# shades_v30.net
KiCad netlist of a schematic drawn in EAGLE
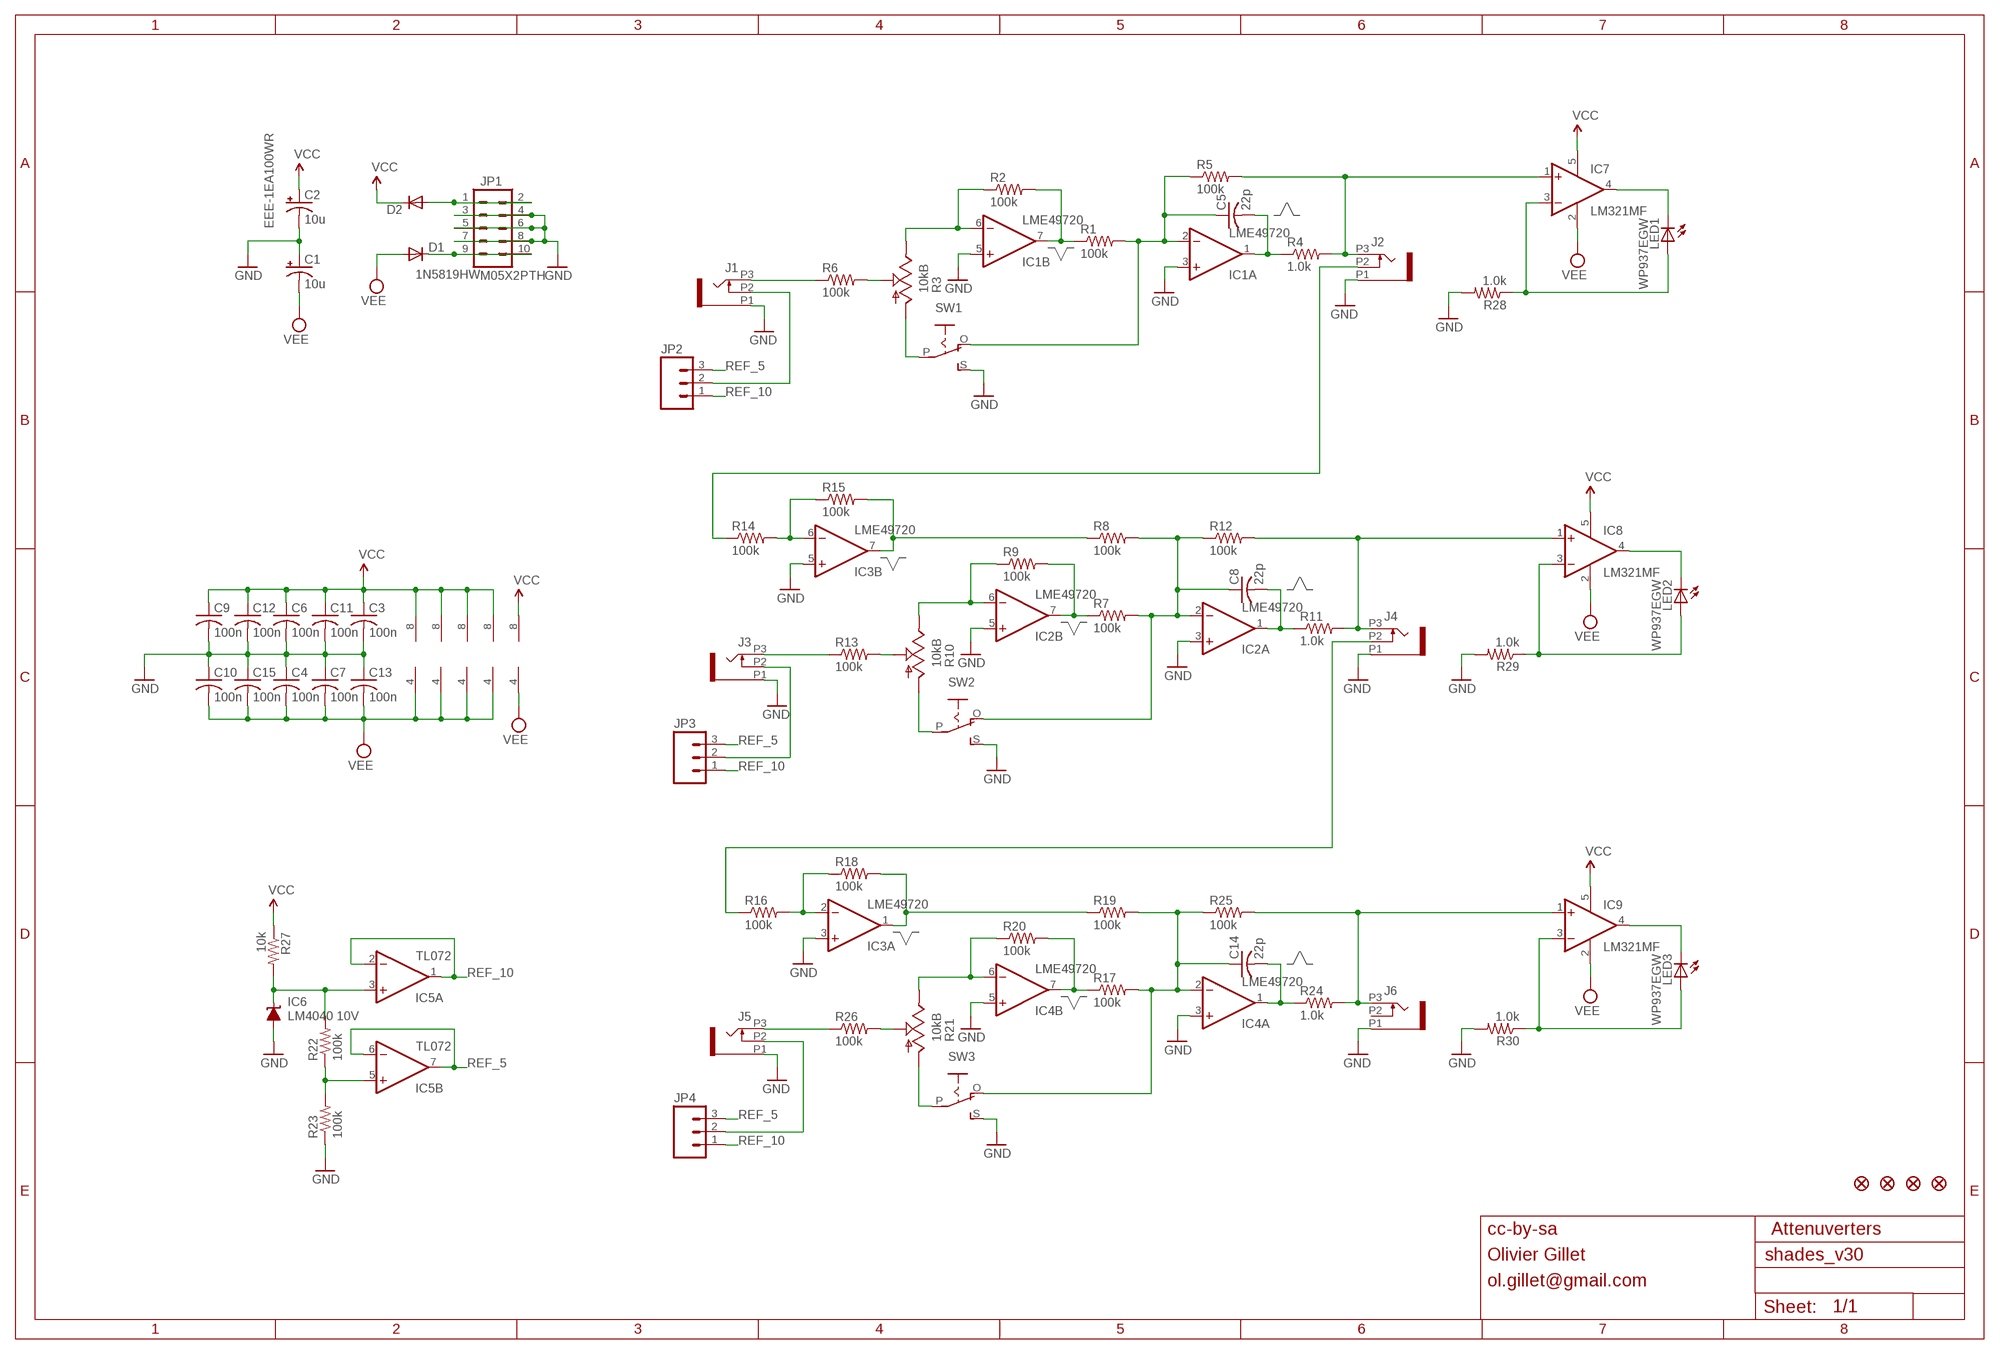
[diagram p0: schematic, sheet 1]

(export (version "E")
  (design (tool "Eeschema 10.0.6"))
  (components
    (comp (ref "C1")
      (value "10u")
      (footprint "eagle-import:PANASONIC_B")
      (libsource (lib "eagle-import") (part "CPOL-USB"))
    )
    (comp (ref "C2")
      (value "10u")
      (footprint "eagle-import:PANASONIC_B")
      (libsource (lib "eagle-import") (part "CPOL-USB"))
    )
    (comp (ref "C3")
      (value "100n")
      (footprint "eagle-import:C0603")
      (libsource (lib "eagle-import") (part "C-USC0603"))
    )
    (comp (ref "C4")
      (value "100n")
      (footprint "eagle-import:C0603")
      (libsource (lib "eagle-import") (part "C-USC0603"))
    )
    (comp (ref "C5")
      (value "22p")
      (footprint "eagle-import:C0603")
      (libsource (lib "eagle-import") (part "C-USC0603"))
    )
    (comp (ref "C6")
      (value "100n")
      (footprint "eagle-import:C0603")
      (libsource (lib "eagle-import") (part "C-USC0603"))
    )
    (comp (ref "C7")
      (value "100n")
      (footprint "eagle-import:C0603")
      (libsource (lib "eagle-import") (part "C-USC0603"))
    )
    (comp (ref "C8")
      (value "22p")
      (footprint "eagle-import:C0603")
      (libsource (lib "eagle-import") (part "C-USC0603"))
    )
    (comp (ref "C9")
      (value "100n")
      (footprint "eagle-import:C0603")
      (libsource (lib "eagle-import") (part "C-USC0603"))
    )
    (comp (ref "C10")
      (value "100n")
      (footprint "eagle-import:C0603")
      (libsource (lib "eagle-import") (part "C-USC0603"))
    )
    (comp (ref "C11")
      (value "100n")
      (footprint "eagle-import:C0603")
      (libsource (lib "eagle-import") (part "C-USC0603"))
    )
    (comp (ref "C12")
      (value "100n")
      (footprint "eagle-import:C0603")
      (libsource (lib "eagle-import") (part "C-USC0603"))
    )
    (comp (ref "C13")
      (value "100n")
      (footprint "eagle-import:C0603")
      (libsource (lib "eagle-import") (part "C-USC0603"))
    )
    (comp (ref "C14")
      (value "22p")
      (footprint "eagle-import:C0603")
      (libsource (lib "eagle-import") (part "C-USC0603"))
    )
    (comp (ref "C15")
      (value "100n")
      (footprint "eagle-import:C0603")
      (libsource (lib "eagle-import") (part "C-USC0603"))
    )
    (comp (ref "D1")
      (value "1N5819HW")
      (footprint "eagle-import:SOD123")
      (libsource (lib "eagle-import") (part "DIODE-SOD123"))
    )
    (comp (ref "D2")
      (value "1N5819HW")
      (footprint "eagle-import:SOD123")
      (libsource (lib "eagle-import") (part "DIODE-SOD123"))
    )
    (comp (ref "F1")
      (value "FIDUCIAL1X2")
      (footprint "eagle-import:FIDUCIAL-1X2")
      (libsource (lib "eagle-import") (part "FIDUCIAL1X2"))
    )
    (comp (ref "F2")
      (value "FIDUCIAL1X2")
      (footprint "eagle-import:FIDUCIAL-1X2")
      (libsource (lib "eagle-import") (part "FIDUCIAL1X2"))
    )
    (comp (ref "F3")
      (value "FIDUCIAL1X2")
      (footprint "eagle-import:FIDUCIAL-1X2")
      (libsource (lib "eagle-import") (part "FIDUCIAL1X2"))
    )
    (comp (ref "F4")
      (value "FIDUCIAL1X2")
      (footprint "eagle-import:FIDUCIAL-1X2")
      (libsource (lib "eagle-import") (part "FIDUCIAL1X2"))
    )
    (comp (ref "IC1")
      (value "LME49720")
      (footprint "eagle-import:SO08")
      (libsource (lib "eagle-import") (part "TL072D"))
    )
    (comp (ref "IC2")
      (value "LME49720")
      (footprint "eagle-import:SO08")
      (libsource (lib "eagle-import") (part "TL072D"))
    )
    (comp (ref "IC3")
      (value "LME49720")
      (footprint "eagle-import:SO08")
      (libsource (lib "eagle-import") (part "TL072D"))
    )
    (comp (ref "IC4")
      (value "LME49720")
      (footprint "eagle-import:SO08")
      (libsource (lib "eagle-import") (part "TL072D"))
    )
    (comp (ref "IC5")
      (value "TL072")
      (footprint "eagle-import:SO08")
      (libsource (lib "eagle-import") (part "TL072D"))
    )
    (comp (ref "IC6")
      (value "LM4040 10V")
      (footprint "eagle-import:DBZ_R-PDSO-G3")
      (libsource (lib "eagle-import") (part "LM4041DBZC12"))
    )
    (comp (ref "IC7")
      (value "LM321MF")
      (footprint "eagle-import:SOT23-5")
      (libsource (lib "eagle-import") (part "LM321?MF"))
    )
    (comp (ref "IC8")
      (value "LM321MF")
      (footprint "eagle-import:SOT23-5")
      (libsource (lib "eagle-import") (part "LM321?MF"))
    )
    (comp (ref "IC9")
      (value "LM321MF")
      (footprint "eagle-import:SOT23-5")
      (libsource (lib "eagle-import") (part "LM321?MF"))
    )
    (comp (ref "J1")
      (value "PJ301_THONKICONN6")
      (footprint "eagle-import:WQP_PJ_301M6")
      (libsource (lib "eagle-import") (part "PJ301_THONKICONN6"))
    )
    (comp (ref "J2")
      (value "PJ301_THONKICONN6")
      (footprint "eagle-import:WQP_PJ_301M6")
      (libsource (lib "eagle-import") (part "PJ301_THONKICONN6"))
    )
    (comp (ref "J3")
      (value "PJ301_THONKICONN6")
      (footprint "eagle-import:WQP_PJ_301M6")
      (libsource (lib "eagle-import") (part "PJ301_THONKICONN6"))
    )
    (comp (ref "J4")
      (value "PJ301_THONKICONN6")
      (footprint "eagle-import:WQP_PJ_301M6")
      (libsource (lib "eagle-import") (part "PJ301_THONKICONN6"))
    )
    (comp (ref "J5")
      (value "PJ301_THONKICONN6")
      (footprint "eagle-import:WQP_PJ_301M6")
      (libsource (lib "eagle-import") (part "PJ301_THONKICONN6"))
    )
    (comp (ref "J6")
      (value "PJ301_THONKICONN6")
      (footprint "eagle-import:WQP_PJ_301M6")
      (libsource (lib "eagle-import") (part "PJ301_THONKICONN6"))
    )
    (comp (ref "JP1")
      (value "M05X2PTH")
      (footprint "eagle-import:AVR_ICSP")
      (libsource (lib "eagle-import") (part "M05X2PTH"))
    )
    (comp (ref "JP2")
      (value "M03PTH")
      (footprint "eagle-import:1X03")
      (libsource (lib "eagle-import") (part "M03PTH"))
    )
    (comp (ref "JP3")
      (value "M03PTH")
      (footprint "eagle-import:1X03")
      (libsource (lib "eagle-import") (part "M03PTH"))
    )
    (comp (ref "JP4")
      (value "M03PTH")
      (footprint "eagle-import:1X03")
      (libsource (lib "eagle-import") (part "M03PTH"))
    )
    (comp (ref "LED1")
      (value "WP937EGW")
      (footprint "eagle-import:LED3MM")
      (libsource (lib "eagle-import") (part "LED3MM"))
    )
    (comp (ref "LED2")
      (value "WP937EGW")
      (footprint "eagle-import:LED3MM")
      (libsource (lib "eagle-import") (part "LED3MM"))
    )
    (comp (ref "LED3")
      (value "WP937EGW")
      (footprint "eagle-import:LED3MM")
      (libsource (lib "eagle-import") (part "LED3MM"))
    )
    (comp (ref "R1")
      (value "100k")
      (footprint "eagle-import:R0603")
      (libsource (lib "eagle-import") (part "R-US_R0603"))
    )
    (comp (ref "R2")
      (value "100k")
      (footprint "eagle-import:R0603")
      (libsource (lib "eagle-import") (part "R-US_R0603"))
    )
    (comp (ref "R3")
      (value "10kB")
      (footprint "eagle-import:ALPS_POT_VERTICAL_PS")
      (libsource (lib "eagle-import") (part "POT_USVERTICAL_PS"))
    )
    (comp (ref "R4")
      (value "1.0k")
      (footprint "eagle-import:R0603")
      (libsource (lib "eagle-import") (part "R-US_R0603"))
    )
    (comp (ref "R5")
      (value "100k")
      (footprint "eagle-import:R0603")
      (libsource (lib "eagle-import") (part "R-US_R0603"))
    )
    (comp (ref "R6")
      (value "100k")
      (footprint "eagle-import:R0603")
      (libsource (lib "eagle-import") (part "R-US_R0603"))
    )
    (comp (ref "R7")
      (value "100k")
      (footprint "eagle-import:R0603")
      (libsource (lib "eagle-import") (part "R-US_R0603"))
    )
    (comp (ref "R8")
      (value "100k")
      (footprint "eagle-import:R0603")
      (libsource (lib "eagle-import") (part "R-US_R0603"))
    )
    (comp (ref "R9")
      (value "100k")
      (footprint "eagle-import:R0603")
      (libsource (lib "eagle-import") (part "R-US_R0603"))
    )
    (comp (ref "R10")
      (value "10kB")
      (footprint "eagle-import:ALPS_POT_VERTICAL_PS")
      (libsource (lib "eagle-import") (part "POT_USVERTICAL_PS"))
    )
    (comp (ref "R11")
      (value "1.0k")
      (footprint "eagle-import:R0603")
      (libsource (lib "eagle-import") (part "R-US_R0603"))
    )
    (comp (ref "R12")
      (value "100k")
      (footprint "eagle-import:R0603")
      (libsource (lib "eagle-import") (part "R-US_R0603"))
    )
    (comp (ref "R13")
      (value "100k")
      (footprint "eagle-import:R0603")
      (libsource (lib "eagle-import") (part "R-US_R0603"))
    )
    (comp (ref "R14")
      (value "100k")
      (footprint "eagle-import:R0603")
      (libsource (lib "eagle-import") (part "R-US_R0603"))
    )
    (comp (ref "R15")
      (value "100k")
      (footprint "eagle-import:R0603")
      (libsource (lib "eagle-import") (part "R-US_R0603"))
    )
    (comp (ref "R16")
      (value "100k")
      (footprint "eagle-import:R0603")
      (libsource (lib "eagle-import") (part "R-US_R0603"))
    )
    (comp (ref "R17")
      (value "100k")
      (footprint "eagle-import:R0603")
      (libsource (lib "eagle-import") (part "R-US_R0603"))
    )
    (comp (ref "R18")
      (value "100k")
      (footprint "eagle-import:R0603")
      (libsource (lib "eagle-import") (part "R-US_R0603"))
    )
    (comp (ref "R19")
      (value "100k")
      (footprint "eagle-import:R0603")
      (libsource (lib "eagle-import") (part "R-US_R0603"))
    )
    (comp (ref "R20")
      (value "100k")
      (footprint "eagle-import:R0603")
      (libsource (lib "eagle-import") (part "R-US_R0603"))
    )
    (comp (ref "R21")
      (value "10kB")
      (footprint "eagle-import:ALPS_POT_VERTICAL_PS")
      (libsource (lib "eagle-import") (part "POT_USVERTICAL_PS"))
    )
    (comp (ref "R22")
      (value "100k")
      (footprint "eagle-import:R0603")
      (libsource (lib "eagle-import") (part "R-US_R0603"))
    )
    (comp (ref "R23")
      (value "100k")
      (footprint "eagle-import:R0603")
      (libsource (lib "eagle-import") (part "R-US_R0603"))
    )
    (comp (ref "R24")
      (value "1.0k")
      (footprint "eagle-import:R0603")
      (libsource (lib "eagle-import") (part "R-US_R0603"))
    )
    (comp (ref "R25")
      (value "100k")
      (footprint "eagle-import:R0603")
      (libsource (lib "eagle-import") (part "R-US_R0603"))
    )
    (comp (ref "R26")
      (value "100k")
      (footprint "eagle-import:R0603")
      (libsource (lib "eagle-import") (part "R-US_R0603"))
    )
    (comp (ref "R27")
      (value "10k")
      (footprint "eagle-import:R0603")
      (libsource (lib "eagle-import") (part "resistor_R-US_R0603"))
    )
    (comp (ref "R28")
      (value "1.0k")
      (footprint "eagle-import:R0603")
      (libsource (lib "eagle-import") (part "R-US_R0603"))
    )
    (comp (ref "R29")
      (value "1.0k")
      (footprint "eagle-import:R0603")
      (libsource (lib "eagle-import") (part "R-US_R0603"))
    )
    (comp (ref "R30")
      (value "1.0k")
      (footprint "eagle-import:R0603")
      (libsource (lib "eagle-import") (part "R-US_R0603"))
    )
    (comp (ref "SW1")
      (value "S-ON-ONSMALL_SLIDE")
      (footprint "eagle-import:ES_100SP1T6B11M2QEH_SMALL")
      (libsource (lib "eagle-import") (part "S-ON-ONSMALL_SLIDE"))
    )
    (comp (ref "SW2")
      (value "S-ON-ONSMALL_SLIDE")
      (footprint "eagle-import:ES_100SP1T6B11M2QEH_SMALL")
      (libsource (lib "eagle-import") (part "S-ON-ONSMALL_SLIDE"))
    )
    (comp (ref "SW3")
      (value "S-ON-ONSMALL_SLIDE")
      (footprint "eagle-import:ES_100SP1T6B11M2QEH_SMALL")
      (libsource (lib "eagle-import") (part "S-ON-ONSMALL_SLIDE"))
    )
  )
  (nets
    (net (code "1") (name "/REF_5") (class "Default")
      (node (ref "IC5") (pin "6") (pinfunction "-IN_6") (pintype "input"))
      (node (ref "IC5") (pin "7") (pinfunction "OUT_7") (pintype "output"))
      (node (ref "JP2") (pin "3") (pinfunction "3_3") (pintype "passive"))
      (node (ref "JP3") (pin "3") (pinfunction "3_3") (pintype "passive"))
      (node (ref "JP4") (pin "3") (pinfunction "3_3") (pintype "passive"))
    )
    (net (code "2") (name "/REF_10") (class "Default")
      (node (ref "IC5") (pin "1") (pinfunction "OUT_1") (pintype "output"))
      (node (ref "IC5") (pin "2") (pinfunction "-IN_2") (pintype "input"))
      (node (ref "JP2") (pin "1") (pinfunction "1_1") (pintype "passive"))
      (node (ref "JP3") (pin "1") (pinfunction "1_1") (pintype "passive"))
      (node (ref "JP4") (pin "1") (pinfunction "1_1") (pintype "passive"))
    )
    (net (code "3") (name "GND") (class "Default")
      (node (ref "C1") (pin "+") (pinfunction "+_+") (pintype "passive"))
      (node (ref "C10") (pin "1") (pinfunction "1_1") (pintype "passive"))
      (node (ref "C11") (pin "2") (pinfunction "2_2") (pintype "passive"))
      (node (ref "C12") (pin "2") (pinfunction "2_2") (pintype "passive"))
      (node (ref "C13") (pin "1") (pinfunction "1_1") (pintype "passive"))
      (node (ref "C15") (pin "1") (pinfunction "1_1") (pintype "passive"))
      (node (ref "C2") (pin "-") (pinfunction "-_-") (pintype "passive"))
      (node (ref "C3") (pin "2") (pinfunction "2_2") (pintype "passive"))
      (node (ref "C4") (pin "1") (pinfunction "1_1") (pintype "passive"))
      (node (ref "C6") (pin "2") (pinfunction "2_2") (pintype "passive"))
      (node (ref "C7") (pin "1") (pinfunction "1_1") (pintype "passive"))
      (node (ref "C9") (pin "2") (pinfunction "2_2") (pintype "passive"))
      (node (ref "IC1") (pin "3") (pinfunction "+IN_3") (pintype "input"))
      (node (ref "IC1") (pin "5") (pinfunction "+IN_5") (pintype "input"))
      (node (ref "IC2") (pin "3") (pinfunction "+IN_3") (pintype "input"))
      (node (ref "IC2") (pin "5") (pinfunction "+IN_5") (pintype "input"))
      (node (ref "IC3") (pin "3") (pinfunction "+IN_3") (pintype "input"))
      (node (ref "IC3") (pin "5") (pinfunction "+IN_5") (pintype "input"))
      (node (ref "IC4") (pin "3") (pinfunction "+IN_3") (pintype "input"))
      (node (ref "IC4") (pin "5") (pinfunction "+IN_5") (pintype "input"))
      (node (ref "IC6") (pin "2") (pinfunction "A_2") (pintype "passive"))
      (node (ref "J1") (pin "P1") (pinfunction "1_P1") (pintype "passive"))
      (node (ref "J2") (pin "P1") (pinfunction "1_P1") (pintype "passive"))
      (node (ref "J3") (pin "P1") (pinfunction "1_P1") (pintype "passive"))
      (node (ref "J4") (pin "P1") (pinfunction "1_P1") (pintype "passive"))
      (node (ref "J5") (pin "P1") (pinfunction "1_P1") (pintype "passive"))
      (node (ref "J6") (pin "P1") (pinfunction "1_P1") (pintype "passive"))
      (node (ref "JP1") (pin "3") (pinfunction "3_3") (pintype "passive"))
      (node (ref "JP1") (pin "4") (pinfunction "4_4") (pintype "passive"))
      (node (ref "JP1") (pin "5") (pinfunction "5_5") (pintype "passive"))
      (node (ref "JP1") (pin "6") (pinfunction "6_6") (pintype "passive"))
      (node (ref "JP1") (pin "7") (pinfunction "7_7") (pintype "passive"))
      (node (ref "JP1") (pin "8") (pinfunction "8_8") (pintype "passive"))
      (node (ref "R23") (pin "1") (pinfunction "1_1") (pintype "passive"))
      (node (ref "R28") (pin "2") (pinfunction "2_2") (pintype "passive"))
      (node (ref "R29") (pin "2") (pinfunction "2_2") (pintype "passive"))
      (node (ref "R30") (pin "2") (pinfunction "2_2") (pintype "passive"))
      (node (ref "SW1") (pin "S") (pinfunction "S_S") (pintype "passive"))
      (node (ref "SW2") (pin "S") (pinfunction "S_S") (pintype "passive"))
      (node (ref "SW3") (pin "S") (pinfunction "S_S") (pintype "passive"))
    )
    (net (code "4") (name "Net-(D1-PadC)") (class "Default")
      (node (ref "D1") (pin "C") (pinfunction "C_C") (pintype "passive"))
      (node (ref "JP1") (pin "10") (pinfunction "10_10") (pintype "passive"))
      (node (ref "JP1") (pin "9") (pinfunction "9_9") (pintype "passive"))
    )
    (net (code "5") (name "Net-(D2-PadA)") (class "Default")
      (node (ref "D2") (pin "A") (pinfunction "A_A") (pintype "passive"))
      (node (ref "JP1") (pin "1") (pinfunction "1_1") (pintype "passive"))
      (node (ref "JP1") (pin "2") (pinfunction "2_2") (pintype "passive"))
    )
    (net (code "6") (name "Net-(IC1A--IN)") (class "Default")
      (node (ref "C5") (pin "1") (pinfunction "1_1") (pintype "passive"))
      (node (ref "IC1") (pin "2") (pinfunction "-IN_2") (pintype "input"))
      (node (ref "R1") (pin "2") (pinfunction "2_2") (pintype "passive"))
      (node (ref "R5") (pin "1") (pinfunction "1_1") (pintype "passive"))
      (node (ref "SW1") (pin "O") (pinfunction "O_O") (pintype "passive"))
    )
    (net (code "7") (name "Net-(IC1A-OUT)") (class "Default")
      (node (ref "C5") (pin "2") (pinfunction "2_2") (pintype "passive"))
      (node (ref "IC1") (pin "1") (pinfunction "OUT_1") (pintype "output"))
      (node (ref "R4") (pin "1") (pinfunction "1_1") (pintype "passive"))
    )
    (net (code "8") (name "Net-(IC1B--IN)") (class "Default")
      (node (ref "IC1") (pin "6") (pinfunction "-IN_6") (pintype "input"))
      (node (ref "R2") (pin "1") (pinfunction "1_1") (pintype "passive"))
      (node (ref "R3") (pin "P$1") (pinfunction "E_P$1") (pintype "passive"))
    )
    (net (code "9") (name "Net-(IC1B-OUT)") (class "Default")
      (node (ref "IC1") (pin "7") (pinfunction "OUT_7") (pintype "output"))
      (node (ref "R1") (pin "1") (pinfunction "1_1") (pintype "passive"))
      (node (ref "R2") (pin "2") (pinfunction "2_2") (pintype "passive"))
    )
    (net (code "10") (name "Net-(IC2A--IN)") (class "Default")
      (node (ref "C8") (pin "1") (pinfunction "1_1") (pintype "passive"))
      (node (ref "IC2") (pin "2") (pinfunction "-IN_2") (pintype "input"))
      (node (ref "R12") (pin "1") (pinfunction "1_1") (pintype "passive"))
      (node (ref "R7") (pin "2") (pinfunction "2_2") (pintype "passive"))
      (node (ref "R8") (pin "2") (pinfunction "2_2") (pintype "passive"))
      (node (ref "SW2") (pin "O") (pinfunction "O_O") (pintype "passive"))
    )
    (net (code "11") (name "Net-(IC2A-OUT)") (class "Default")
      (node (ref "C8") (pin "2") (pinfunction "2_2") (pintype "passive"))
      (node (ref "IC2") (pin "1") (pinfunction "OUT_1") (pintype "output"))
      (node (ref "R11") (pin "1") (pinfunction "1_1") (pintype "passive"))
    )
    (net (code "12") (name "Net-(IC2B--IN)") (class "Default")
      (node (ref "IC2") (pin "6") (pinfunction "-IN_6") (pintype "input"))
      (node (ref "R10") (pin "P$1") (pinfunction "E_P$1") (pintype "passive"))
      (node (ref "R9") (pin "1") (pinfunction "1_1") (pintype "passive"))
    )
    (net (code "13") (name "Net-(IC2B-OUT)") (class "Default")
      (node (ref "IC2") (pin "7") (pinfunction "OUT_7") (pintype "output"))
      (node (ref "R7") (pin "1") (pinfunction "1_1") (pintype "passive"))
      (node (ref "R9") (pin "2") (pinfunction "2_2") (pintype "passive"))
    )
    (net (code "14") (name "Net-(IC3A--IN)") (class "Default")
      (node (ref "IC3") (pin "2") (pinfunction "-IN_2") (pintype "input"))
      (node (ref "R16") (pin "2") (pinfunction "2_2") (pintype "passive"))
      (node (ref "R18") (pin "1") (pinfunction "1_1") (pintype "passive"))
    )
    (net (code "15") (name "Net-(IC3A-OUT)") (class "Default")
      (node (ref "IC3") (pin "1") (pinfunction "OUT_1") (pintype "output"))
      (node (ref "R18") (pin "2") (pinfunction "2_2") (pintype "passive"))
      (node (ref "R19") (pin "1") (pinfunction "1_1") (pintype "passive"))
    )
    (net (code "16") (name "Net-(IC3B--IN)") (class "Default")
      (node (ref "IC3") (pin "6") (pinfunction "-IN_6") (pintype "input"))
      (node (ref "R14") (pin "2") (pinfunction "2_2") (pintype "passive"))
      (node (ref "R15") (pin "1") (pinfunction "1_1") (pintype "passive"))
    )
    (net (code "17") (name "Net-(IC3B-OUT)") (class "Default")
      (node (ref "IC3") (pin "7") (pinfunction "OUT_7") (pintype "output"))
      (node (ref "R15") (pin "2") (pinfunction "2_2") (pintype "passive"))
      (node (ref "R8") (pin "1") (pinfunction "1_1") (pintype "passive"))
    )
    (net (code "18") (name "Net-(IC4A--IN)") (class "Default")
      (node (ref "C14") (pin "1") (pinfunction "1_1") (pintype "passive"))
      (node (ref "IC4") (pin "2") (pinfunction "-IN_2") (pintype "input"))
      (node (ref "R17") (pin "2") (pinfunction "2_2") (pintype "passive"))
      (node (ref "R19") (pin "2") (pinfunction "2_2") (pintype "passive"))
      (node (ref "R25") (pin "1") (pinfunction "1_1") (pintype "passive"))
      (node (ref "SW3") (pin "O") (pinfunction "O_O") (pintype "passive"))
    )
    (net (code "19") (name "Net-(IC4A-OUT)") (class "Default")
      (node (ref "C14") (pin "2") (pinfunction "2_2") (pintype "passive"))
      (node (ref "IC4") (pin "1") (pinfunction "OUT_1") (pintype "output"))
      (node (ref "R24") (pin "1") (pinfunction "1_1") (pintype "passive"))
    )
    (net (code "20") (name "Net-(IC4B--IN)") (class "Default")
      (node (ref "IC4") (pin "6") (pinfunction "-IN_6") (pintype "input"))
      (node (ref "R20") (pin "1") (pinfunction "1_1") (pintype "passive"))
      (node (ref "R21") (pin "P$1") (pinfunction "E_P$1") (pintype "passive"))
    )
    (net (code "21") (name "Net-(IC4B-OUT)") (class "Default")
      (node (ref "IC4") (pin "7") (pinfunction "OUT_7") (pintype "output"))
      (node (ref "R17") (pin "1") (pinfunction "1_1") (pintype "passive"))
      (node (ref "R20") (pin "2") (pinfunction "2_2") (pintype "passive"))
    )
    (net (code "22") (name "Net-(IC5A-+IN)") (class "Default")
      (node (ref "IC5") (pin "3") (pinfunction "+IN_3") (pintype "input"))
      (node (ref "IC6") (pin "1") (pinfunction "C_1") (pintype "passive"))
      (node (ref "R22") (pin "2") (pinfunction "2_2") (pintype "passive"))
      (node (ref "R27") (pin "2") (pinfunction "2_2") (pintype "passive"))
    )
    (net (code "23") (name "Net-(IC5B-+IN)") (class "Default")
      (node (ref "IC5") (pin "5") (pinfunction "+IN_5") (pintype "input"))
      (node (ref "R22") (pin "1") (pinfunction "1_1") (pintype "passive"))
      (node (ref "R23") (pin "2") (pinfunction "2_2") (pintype "passive"))
    )
    (net (code "24") (name "Net-(IC7-+IN)") (class "Default")
      (node (ref "IC7") (pin "1") (pinfunction "+IN_1") (pintype "input"))
      (node (ref "J2") (pin "P3") (pinfunction "3_P3") (pintype "passive"))
      (node (ref "R4") (pin "2") (pinfunction "2_2") (pintype "passive"))
      (node (ref "R5") (pin "2") (pinfunction "2_2") (pintype "passive"))
    )
    (net (code "25") (name "Net-(IC7--IN)") (class "Default")
      (node (ref "IC7") (pin "3") (pinfunction "-IN_3") (pintype "input"))
      (node (ref "LED1") (pin "A") (pinfunction "A_A") (pintype "passive"))
      (node (ref "R28") (pin "1") (pinfunction "1_1") (pintype "passive"))
    )
    (net (code "26") (name "Net-(IC7-OUT)") (class "Default")
      (node (ref "IC7") (pin "4") (pinfunction "OUT_4") (pintype "output"))
      (node (ref "LED1") (pin "K") (pinfunction "C_K") (pintype "passive"))
    )
    (net (code "27") (name "Net-(IC8-+IN)") (class "Default")
      (node (ref "IC8") (pin "1") (pinfunction "+IN_1") (pintype "input"))
      (node (ref "J4") (pin "P3") (pinfunction "3_P3") (pintype "passive"))
      (node (ref "R11") (pin "2") (pinfunction "2_2") (pintype "passive"))
      (node (ref "R12") (pin "2") (pinfunction "2_2") (pintype "passive"))
    )
    (net (code "28") (name "Net-(IC8--IN)") (class "Default")
      (node (ref "IC8") (pin "3") (pinfunction "-IN_3") (pintype "input"))
      (node (ref "LED2") (pin "A") (pinfunction "A_A") (pintype "passive"))
      (node (ref "R29") (pin "1") (pinfunction "1_1") (pintype "passive"))
    )
    (net (code "29") (name "Net-(IC8-OUT)") (class "Default")
      (node (ref "IC8") (pin "4") (pinfunction "OUT_4") (pintype "output"))
      (node (ref "LED2") (pin "K") (pinfunction "C_K") (pintype "passive"))
    )
    (net (code "30") (name "Net-(IC9-+IN)") (class "Default")
      (node (ref "IC9") (pin "1") (pinfunction "+IN_1") (pintype "input"))
      (node (ref "J6") (pin "P3") (pinfunction "3_P3") (pintype "passive"))
      (node (ref "R24") (pin "2") (pinfunction "2_2") (pintype "passive"))
      (node (ref "R25") (pin "2") (pinfunction "2_2") (pintype "passive"))
    )
    (net (code "31") (name "Net-(IC9--IN)") (class "Default")
      (node (ref "IC9") (pin "3") (pinfunction "-IN_3") (pintype "input"))
      (node (ref "LED3") (pin "A") (pinfunction "A_A") (pintype "passive"))
      (node (ref "R30") (pin "1") (pinfunction "1_1") (pintype "passive"))
    )
    (net (code "32") (name "Net-(IC9-OUT)") (class "Default")
      (node (ref "IC9") (pin "4") (pinfunction "OUT_4") (pintype "output"))
      (node (ref "LED3") (pin "K") (pinfunction "C_K") (pintype "passive"))
    )
    (net (code "33") (name "Net-(J1-2)") (class "Default")
      (node (ref "J1") (pin "P2") (pinfunction "2_P2") (pintype "passive"))
      (node (ref "JP2") (pin "2") (pinfunction "2_2") (pintype "passive"))
    )
    (net (code "34") (name "Net-(J1-3)") (class "Default")
      (node (ref "J1") (pin "P3") (pinfunction "3_P3") (pintype "passive"))
      (node (ref "R6") (pin "1") (pinfunction "1_1") (pintype "passive"))
    )
    (net (code "35") (name "Net-(J2-2)") (class "Default")
      (node (ref "J2") (pin "P2") (pinfunction "2_P2") (pintype "passive"))
      (node (ref "R14") (pin "1") (pinfunction "1_1") (pintype "passive"))
    )
    (net (code "36") (name "Net-(J3-2)") (class "Default")
      (node (ref "J3") (pin "P2") (pinfunction "2_P2") (pintype "passive"))
      (node (ref "JP3") (pin "2") (pinfunction "2_2") (pintype "passive"))
    )
    (net (code "37") (name "Net-(J3-3)") (class "Default")
      (node (ref "J3") (pin "P3") (pinfunction "3_P3") (pintype "passive"))
      (node (ref "R13") (pin "1") (pinfunction "1_1") (pintype "passive"))
    )
    (net (code "38") (name "Net-(J4-2)") (class "Default")
      (node (ref "J4") (pin "P2") (pinfunction "2_P2") (pintype "passive"))
      (node (ref "R16") (pin "1") (pinfunction "1_1") (pintype "passive"))
    )
    (net (code "39") (name "Net-(J5-2)") (class "Default")
      (node (ref "J5") (pin "P2") (pinfunction "2_P2") (pintype "passive"))
      (node (ref "JP4") (pin "2") (pinfunction "2_2") (pintype "passive"))
    )
    (net (code "40") (name "Net-(J5-3)") (class "Default")
      (node (ref "J5") (pin "P3") (pinfunction "3_P3") (pintype "passive"))
      (node (ref "R26") (pin "1") (pinfunction "1_1") (pintype "passive"))
    )
    (net (code "41") (name "Net-(R3-A)") (class "Default")
      (node (ref "R3") (pin "P$3") (pinfunction "A_P$3") (pintype "passive"))
      (node (ref "SW1") (pin "P") (pinfunction "P_P") (pintype "passive"))
    )
    (net (code "42") (name "Net-(R3-S)") (class "Default")
      (node (ref "R3") (pin "P$2") (pinfunction "S_P$2") (pintype "passive"))
      (node (ref "R6") (pin "2") (pinfunction "2_2") (pintype "passive"))
    )
    (net (code "43") (name "Net-(R10-A)") (class "Default")
      (node (ref "R10") (pin "P$3") (pinfunction "A_P$3") (pintype "passive"))
      (node (ref "SW2") (pin "P") (pinfunction "P_P") (pintype "passive"))
    )
    (net (code "44") (name "Net-(R10-S)") (class "Default")
      (node (ref "R10") (pin "P$2") (pinfunction "S_P$2") (pintype "passive"))
      (node (ref "R13") (pin "2") (pinfunction "2_2") (pintype "passive"))
    )
    (net (code "45") (name "Net-(R21-A)") (class "Default")
      (node (ref "R21") (pin "P$3") (pinfunction "A_P$3") (pintype "passive"))
      (node (ref "SW3") (pin "P") (pinfunction "P_P") (pintype "passive"))
    )
    (net (code "46") (name "Net-(R21-S)") (class "Default")
      (node (ref "R21") (pin "P$2") (pinfunction "S_P$2") (pintype "passive"))
      (node (ref "R26") (pin "2") (pinfunction "2_2") (pintype "passive"))
    )
    (net (code "47") (name "VCC") (class "Default")
      (node (ref "C11") (pin "1") (pinfunction "1_1") (pintype "passive"))
      (node (ref "C12") (pin "1") (pinfunction "1_1") (pintype "passive"))
      (node (ref "C2") (pin "+") (pinfunction "+_+") (pintype "passive"))
      (node (ref "C3") (pin "1") (pinfunction "1_1") (pintype "passive"))
      (node (ref "C6") (pin "1") (pinfunction "1_1") (pintype "passive"))
      (node (ref "C9") (pin "1") (pinfunction "1_1") (pintype "passive"))
      (node (ref "D2") (pin "C") (pinfunction "C_C") (pintype "passive"))
      (node (ref "IC1") (pin "8") (pinfunction "V+_8") (pintype "power_in"))
      (node (ref "IC2") (pin "8") (pinfunction "V+_8") (pintype "power_in"))
      (node (ref "IC3") (pin "8") (pinfunction "V+_8") (pintype "power_in"))
      (node (ref "IC4") (pin "8") (pinfunction "V+_8") (pintype "power_in"))
      (node (ref "IC5") (pin "8") (pinfunction "V+_8") (pintype "power_in"))
      (node (ref "IC7") (pin "5") (pinfunction "V+_5") (pintype "power_in"))
      (node (ref "IC8") (pin "5") (pinfunction "V+_5") (pintype "power_in"))
      (node (ref "IC9") (pin "5") (pinfunction "V+_5") (pintype "power_in"))
      (node (ref "R27") (pin "1") (pinfunction "1_1") (pintype "passive"))
    )
    (net (code "48") (name "VEE") (class "Default")
      (node (ref "C1") (pin "-") (pinfunction "-_-") (pintype "passive"))
      (node (ref "C10") (pin "2") (pinfunction "2_2") (pintype "passive"))
      (node (ref "C13") (pin "2") (pinfunction "2_2") (pintype "passive"))
      (node (ref "C15") (pin "2") (pinfunction "2_2") (pintype "passive"))
      (node (ref "C4") (pin "2") (pinfunction "2_2") (pintype "passive"))
      (node (ref "C7") (pin "2") (pinfunction "2_2") (pintype "passive"))
      (node (ref "D1") (pin "A") (pinfunction "A_A") (pintype "passive"))
      (node (ref "IC1") (pin "4") (pinfunction "V-_4") (pintype "power_in"))
      (node (ref "IC2") (pin "4") (pinfunction "V-_4") (pintype "power_in"))
      (node (ref "IC3") (pin "4") (pinfunction "V-_4") (pintype "power_in"))
      (node (ref "IC4") (pin "4") (pinfunction "V-_4") (pintype "power_in"))
      (node (ref "IC5") (pin "4") (pinfunction "V-_4") (pintype "power_in"))
      (node (ref "IC7") (pin "2") (pinfunction "V-_2") (pintype "power_in"))
      (node (ref "IC8") (pin "2") (pinfunction "V-_2") (pintype "power_in"))
      (node (ref "IC9") (pin "2") (pinfunction "V-_2") (pintype "power_in"))
    )
    (net (code "49") (name "unconnected-(J6-2-PadP2)") (class "Default")
      (node (ref "J6") (pin "P2") (pinfunction "2_P2") (pintype "passive"))
    )
  )
)
